# PMU.net
KiCad netlist of a schematic drawn in Altium Designer
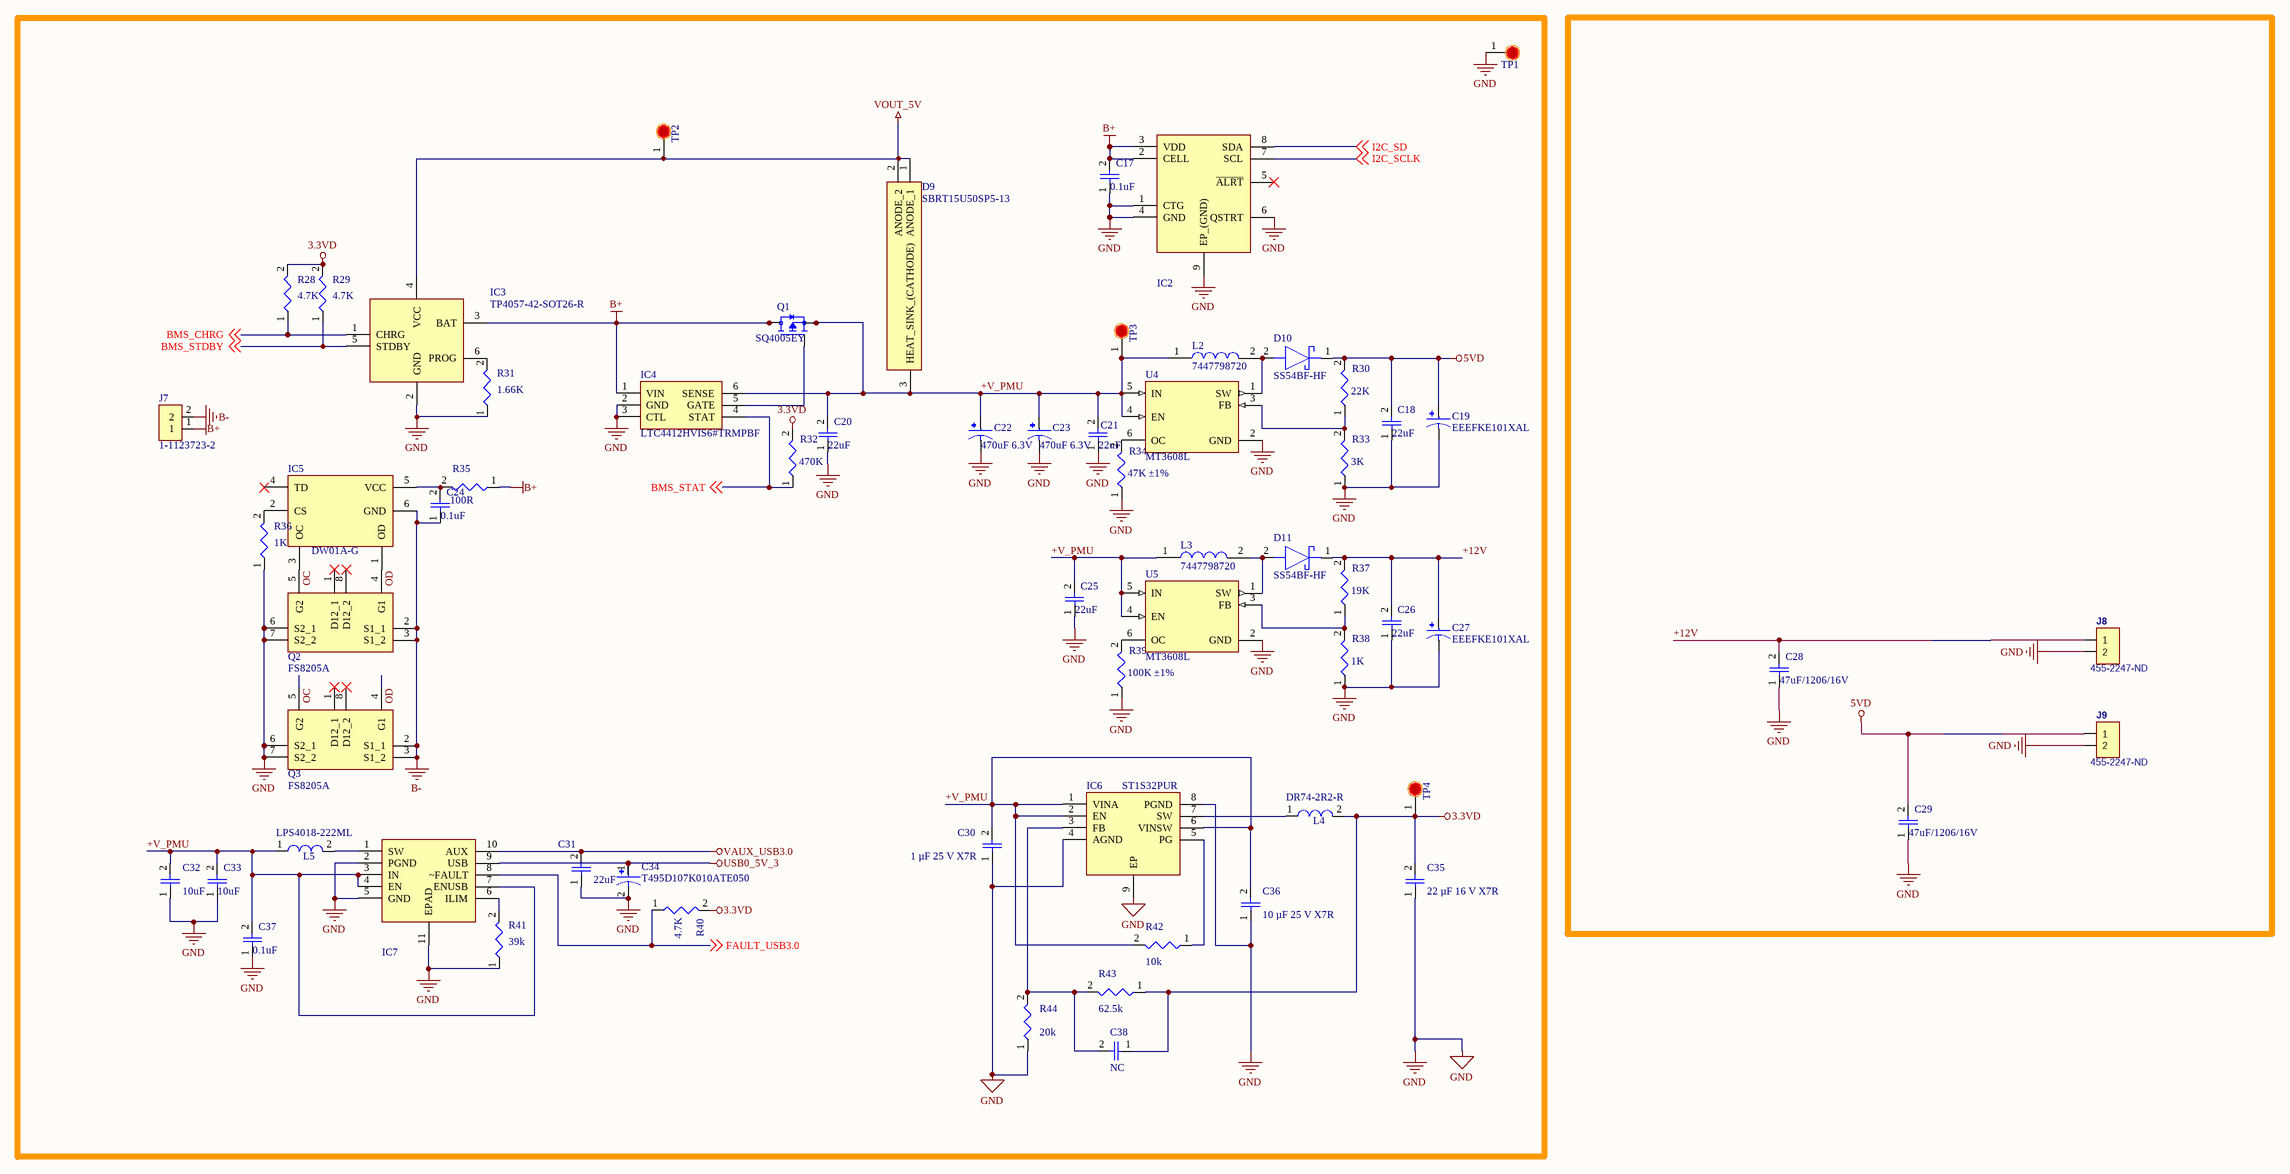
[diagram p0: PMU.SchDoc]

(export (version "E")
  (design (tool "Eeschema 10.0.6"))
  (components
    (comp (ref "C17") (value "0.1uF") (footprint "0603-C") (libsource (lib "OOLITEV8") (part "CAP")))
    (comp (ref "C18") (value "22uF") (footprint "1206-C") (libsource (lib "OOLITEV8") (part "CAP")))
    (comp (ref "C19")
      (value "EEEFKE101XAL")
      (footprint "CAP_EEEFKE101XAL")
      (description "CAP ALUM 100UF 20% 25V SMD")
      (fields (field (name "MF") "Panasonic") (field (name "DIGI-KEY_PART_NUMBER") "10-EEE-FKE101XALCT-ND"))
      (libsource (lib "OOLITEV8") (part "EEEFKE101XAL"))
    )
    (comp (ref "C20") (value "22uF") (footprint "0603-C") (libsource (lib "OOLITEV8") (part "CAP")))
    (comp (ref "C21") (value "22uF") (footprint "0603-C") (libsource (lib "OOLITEV8") (part "CAP")))
    (comp (ref "C22")
      (value "470uF 6.3V")
      (footprint "CAP_EEEFK0J471P")
      (libsource (lib "OOLITEV8") (part "EEEFK0J471P"))
    )
    (comp (ref "C23")
      (value "470uF 6.3V")
      (footprint "CAP_EEEFK0J471P")
      (libsource (lib "OOLITEV8") (part "EEEFK0J471P"))
    )
    (comp (ref "C24") (value "0.1uF") (footprint "0603-C") (libsource (lib "OOLITEV8") (part "CAP")))
    (comp (ref "C25") (value "22uF") (footprint "0603-C") (libsource (lib "OOLITEV8") (part "CAP")))
    (comp (ref "C26") (value "22uF") (footprint "1206-C") (libsource (lib "OOLITEV8") (part "CAP")))
    (comp (ref "C27")
      (value "EEEFKE101XAL")
      (footprint "CAP_EEEFKE101XAL")
      (description "CAP ALUM 100UF 20% 25V SMD")
      (fields (field (name "MF") "Panasonic") (field (name "DIGI-KEY_PART_NUMBER") "10-EEE-FKE101XALCT-ND"))
      (libsource (lib "OOLITEV8") (part "EEEFKE101XAL"))
    )
    (comp (ref "C28") (value "47uF/1206/16V") (footprint "1206-C") (libsource (lib "OOLITEV8") (part "CAP")))
    (comp (ref "C29") (value "47uF/1206/16V") (footprint "1206-C") (libsource (lib "OOLITEV8") (part "CAP")))
    (comp (ref "C30") (value "1 µF 25 V X7R") (footprint "0603-C") (libsource (lib "OOLITEV8") (part "CAP")))
    (comp (ref "C31") (value "22uF") (footprint "1210-C") (libsource (lib "OOLITEV8") (part "CAP")))
    (comp (ref "C32") (value "10uF") (footprint "1210-C") (libsource (lib "OOLITEV8") (part "CAP")))
    (comp (ref "C33") (value "10uF") (footprint "0805-C") (libsource (lib "OOLITEV8") (part "CAP")))
    (comp (ref "C34")
      (value "T495D107K010ATE050")
      (footprint "CAP_4TAE470ML")
      (description "Cap Tant Solid 100uF 10V D CASE 10% (7.3 X 4.3 X 2.8mm) SMD 7343-31 0.05 Ohm 125°C T/R")
      (fields (field (name "MANUFACTURER") "KEMET") (field (name "TOLERANCE") "10%"))
      (libsource (lib "OOLITEV8") (part "T495D107K010ATE050"))
    )
    (comp (ref "C35") (value "22 µF 16 V X7R") (footprint "1210-C") (libsource (lib "OOLITEV8") (part "CAP")))
    (comp (ref "C36") (value "10 µF 25 V X7R") (footprint "1210-C") (libsource (lib "OOLITEV8") (part "CAP")))
    (comp (ref "C37") (value "0.1uF") (footprint "0603-C") (libsource (lib "OOLITEV8") (part "CAP")))
    (comp (ref "C38") (value "NC") (footprint "0603-C") (libsource (lib "OOLITEV8") (part "CAP")))
    (comp (ref "D9")
      (value "SBRT15U50SP5-13")
      (footprint "SamacSys:POWERDI5")
      (description "Diode")
      (fields (field (name "MOUSER PART NUMBER") "621-SBRT15U50SP5-13"))
      (libsource (lib "*") (part "SBRT15U50SP5-13"))
    )
    (comp (ref "D10")
      (value "SS54BF-HF")
      (footprint "SODFL5336X130N")
      (description "Schottky Diode")
      (fields (field (name "MOUSER PART NUMBER") "750-SS54BF-HF"))
      (libsource (lib "OOLITEV8") (part "SS54BF-HF"))
    )
    (comp (ref "D11")
      (value "SS54BF-HF")
      (footprint "SODFL5336X130N")
      (description "Schottky Diode")
      (fields (field (name "MOUSER PART NUMBER") "750-SS54BF-HF"))
      (libsource (lib "OOLITEV8") (part "SS54BF-HF"))
    )
    (comp (ref "IC2")
      (value "MAX17048G+T10")
      (footprint "SON50P200X200X80-9N-D")
      (description "Integrated Circuit")
      (fields (field (name "MOUSER PART NUMBER") "700-MAX17048G+T10"))
      (libsource (lib "OOLITEV8") (part "MAX17048G+T10"))
    )
    (comp (ref "IC3")
      (value "TP4057-42-SOT26-R")
      (footprint "SOT95P280X125-6N")
      (description "Integrated Circuit")
      (libsource (lib "OOLITEV8") (part "TP4057-42-SOT26-R"))
    )
    (comp (ref "IC4")
      (value "LTC4412HVIS6#TRMPBF")
      (footprint "SOT95P280X100-6N")
      (description "Integrated Circuit")
      (fields (field (name "MOUSER PART NUMBER") "584-C4412HVIS6TRMPBF"))
      (libsource (lib "OOLITEV8") (part "LTC4412HVIS6#TRMPBF"))
    )
    (comp (ref "IC5")
      (value "DW01A-G")
      (footprint "SOT95P280X135-6N")
      (description "Integrated Circuit")
      (libsource (lib "OOLITEV8") (part "DW01A-G"))
    )
    (comp (ref "IC6")
      (value "ST1S32PUR")
      (footprint "SON80P400X400X100-9N-D")
      (description "Integrated Circuit")
      (fields (field (name "MOUSER PART NUMBER") "511-ST1S32PUR"))
      (libsource (lib "OOLITEV8") (part "ST1S32PUR"))
    )
    (comp (ref "IC7")
      (value "TPS2500DRCT")
      (footprint "SON50P300X300X100-11N")
      (description "Integrated Circuit")
      (fields (field (name "MOUSER PART NUMBER") "595-TPS2500DRCT"))
      (libsource (lib "OOLITEV8") (part "TPS2500DRCT"))
    )
    (comp (ref "J7")
      (value "1-1123723-2")
      (footprint "TE_1-1123723-2")
      (description "3.96 EP HDR ASSY 2P_NATURAL_")
      (fields (field (name "MF") "TE Connectivity") (field (name "DIGI-KEY_PART_NUMBER") "A111830-ND"))
      (libsource (lib "1-1123723-2") (part "1-1123723-2"))
    )
    (comp (ref "J8")
      (value "455-2247-ND")
      (footprint "CON_HDR1x2")
      (libsource (lib "OOLITEV8") (part "CON_HDR1x2"))
    )
    (comp (ref "J9")
      (value "455-2247-ND")
      (footprint "CON_HDR1x2")
      (libsource (lib "OOLITEV8") (part "CON_HDR1x2"))
    )
    (comp (ref "L2")
      (value "7447798720")
      (footprint "CDRH103RNP6R8NCB")
      (description "Fixed Ind 7.2UH 7.9A 12.8 Mohm")
      (fields (field (name "MANUFACTURER") "Wurth Electronics") (field (name "TOLERANCE") "30%"))
      (libsource (lib "OOLITEV8") (part "7447798720"))
    )
    (comp (ref "L3")
      (value "7447798720")
      (footprint "CDRH103RNP6R8NCB")
      (description "Fixed Ind 7.2UH 7.9A 12.8 Mohm")
      (fields (field (name "MANUFACTURER") "Wurth Electronics") (field (name "TOLERANCE") "30%"))
      (libsource (lib "OOLITEV8") (part "7447798720"))
    )
    (comp (ref "L4")
      (value "DR74-2R2-R")
      (footprint "INDM7676X435N")
      (libsource (lib "OOLITEV8") (part "DR74-2R2-R"))
    )
    (comp (ref "L5")
      (value "LPS4018-222ML")
      (footprint "VLC5045")
      (libsource (lib "OOLITEV8") (part "IND/VLC5045"))
    )
    (comp (ref "Q1")
      (value "SQ4005EY")
      (footprint "SOIC127P600X175-8N")
      (description "MOSFET P Ch -12Vds 8Vgs")
      (libsource (lib "IIOT_GATEWAY_MT7621") (part "SQ4005EY"))
    )
    (comp (ref "Q2")
      (value "FS8205A")
      (footprint "SOP65P640X120-8N")
      (description "Transistor")
      (libsource (lib "OOLITEV8") (part "FS8205A"))
    )
    (comp (ref "Q3")
      (value "FS8205A")
      (footprint "SOP65P640X120-8N")
      (description "Transistor")
      (libsource (lib "OOLITEV8_0_2-DEV-V1_1_17") (part "FS8205A"))
    )
    (comp (ref "R28") (value "4.7K") (footprint "0402-R") (libsource (lib "OOLITEV8") (part "Res")))
    (comp (ref "R29") (value "4.7K") (footprint "0402-R") (libsource (lib "OOLITEV8") (part "Res")))
    (comp (ref "R30") (value "22K") (footprint "0603-R") (libsource (lib "OOLITEV8") (part "Res")))
    (comp (ref "R31") (value "1.66K") (footprint "0603-R") (libsource (lib "OOLITEV8") (part "Res")))
    (comp (ref "R32") (value "470K") (footprint "0402-R") (libsource (lib "OOLITEV8") (part "Res")))
    (comp (ref "R33") (value "3K") (footprint "0603-R") (libsource (lib "OOLITEV8") (part "Res")))
    (comp (ref "R34") (value "47K ±1%") (footprint "0603-R") (libsource (lib "OOLITEV8") (part "Res")))
    (comp (ref "R35") (value "100R") (footprint "0603-R") (libsource (lib "OOLITEV8") (part "Res")))
    (comp (ref "R36") (value "1K") (footprint "0603-R") (libsource (lib "OOLITEV8") (part "Res")))
    (comp (ref "R37") (value "19K") (footprint "0603-R") (libsource (lib "OOLITEV8") (part "Res")))
    (comp (ref "R38") (value "1K") (footprint "0603-R") (libsource (lib "OOLITEV8") (part "Res")))
    (comp (ref "R39") (value "100K ±1%") (footprint "0603-R") (libsource (lib "OOLITEV8") (part "Res")))
    (comp (ref "R40") (value "4.7K") (footprint "0402-R") (libsource (lib "OOLITEV8") (part "Res")))
    (comp (ref "R41") (value "39k") (footprint "0603-R") (libsource (lib "OOLITEV8") (part "Res")))
    (comp (ref "R42") (value "10k") (footprint "0603-R") (libsource (lib "OOLITEV8") (part "Res")))
    (comp (ref "R43") (value "62.5k") (footprint "0603-R") (libsource (lib "OOLITEV8") (part "Res")))
    (comp (ref "R44") (value "20k") (footprint "0603-R") (libsource (lib "OOLITEV8") (part "Res")))
    (comp (ref "TP1") (value "TP") (footprint "TP_SMD") (libsource (lib "OOLITEV8") (part "Test Pad")))
    (comp (ref "TP2") (value "TP") (footprint "TP_SMD") (libsource (lib "OOLITEV8") (part "Test Pad")))
    (comp (ref "TP3") (value "TP") (footprint "TP_SMD") (libsource (lib "OOLITEV8") (part "Test Pad")))
    (comp (ref "TP4") (value "TP") (footprint "TP_SMD") (libsource (lib "OOLITEV8") (part "Test Pad")))
    (comp (ref "U4")
      (value "MT3608L")
      (footprint "SOT95P280X145-6N")
      (description "High Efficiency 1.2MHz2A Step Up Converter")
      (fields (field (name "MF") "Aerosemi Technology Co., Ltd") (field (name "MP") "MT3608"))
      (libsource (lib "OOLITEV8") (part "MT3608L"))
    )
    (comp (ref "U5")
      (value "MT3608L")
      (footprint "SOT95P280X145-6N")
      (description "High Efficiency 1.2MHz2A Step Up Converter")
      (fields (field (name "MF") "Aerosemi Technology Co., Ltd") (field (name "MP") "MT3608"))
      (libsource (lib "OOLITEV8") (part "MT3608L"))
    )
  )
  (nets
    (net (code "1") (name "/+12V") (class "Default")
      (node (ref "C26") (pin "2") (pinfunction "2_2") (pintype "passive"))
      (node (ref "C27") (pin "1") (pinfunction "1_1") (pintype "passive"))
      (node (ref "C28") (pin "2") (pinfunction "2_2") (pintype "passive"))
      (node (ref "D11") (pin "1") (pinfunction "K_1") (pintype "passive"))
      (node (ref "J8") (pin "1") (pinfunction "1_1") (pintype "passive"))
      (node (ref "R37") (pin "2") (pinfunction "2_2") (pintype "passive"))
    )
    (net (code "2") (name "/+V_PMU") (class "Default")
      (node (ref "C20") (pin "2") (pinfunction "2_2") (pintype "passive"))
      (node (ref "C21") (pin "2") (pinfunction "2_2") (pintype "passive"))
      (node (ref "C22") (pin "1") (pinfunction "1_1") (pintype "passive"))
      (node (ref "C23") (pin "1") (pinfunction "1_1") (pintype "passive"))
      (node (ref "C25") (pin "2") (pinfunction "2_2") (pintype "passive"))
      (node (ref "C30") (pin "2") (pinfunction "2_2") (pintype "passive"))
      (node (ref "C32") (pin "2") (pinfunction "2_2") (pintype "passive"))
      (node (ref "C33") (pin "2") (pinfunction "2_2") (pintype "passive"))
      (node (ref "C36") (pin "2") (pinfunction "2_2") (pintype "passive"))
      (node (ref "C37") (pin "2") (pinfunction "2_2") (pintype "passive"))
      (node (ref "D9") (pin "3") (pinfunction "HEAT_SINK_(CATHODE)_3") (pintype "passive"))
      (node (ref "IC4") (pin "6") (pinfunction "SENSE_6") (pintype "passive"))
      (node (ref "IC6") (pin "1") (pinfunction "VINA_1") (pintype "passive"))
      (node (ref "IC6") (pin "2") (pinfunction "EN_2") (pintype "passive"))
      (node (ref "IC6") (pin "6") (pinfunction "VINSW_6") (pintype "passive"))
      (node (ref "IC7") (pin "3") (pinfunction "IN_3") (pintype "passive"))
      (node (ref "IC7") (pin "4") (pinfunction "EN_4") (pintype "passive"))
      (node (ref "IC7") (pin "7") (pinfunction "ENUSB_7") (pintype "passive"))
      (node (ref "L2") (pin "1") (pinfunction "1_1") (pintype "passive"))
      (node (ref "L3") (pin "1") (pinfunction "1_1") (pintype "passive"))
      (node (ref "L5") (pin "1") (pinfunction "1_1") (pintype "passive"))
      (node (ref "Q1") (pin "1") (pinfunction "S_1") (pintype "passive"))
      (node (ref "Q1") (pin "2") (pinfunction "S_2") (pintype "passive"))
      (node (ref "Q1") (pin "3") (pinfunction "S_3") (pintype "passive"))
      (node (ref "R42") (pin "2") (pinfunction "2_2") (pintype "passive"))
      (node (ref "TP3") (pin "1") (pinfunction "1_1") (pintype "passive"))
      (node (ref "U4") (pin "4") (pinfunction "EN_4") (pintype "input"))
      (node (ref "U4") (pin "5") (pinfunction "IN_5") (pintype "input"))
      (node (ref "U5") (pin "4") (pinfunction "EN_4") (pintype "input"))
      (node (ref "U5") (pin "5") (pinfunction "IN_5") (pintype "input"))
    )
    (net (code "3") (name "/OC") (class "Default")
      (node (ref "IC5") (pin "3") (pinfunction "OC_3") (pintype "passive"))
      (node (ref "Q2") (pin "5") (pinfunction "G2_5") (pintype "passive"))
      (node (ref "Q3") (pin "5") (pinfunction "G2_5") (pintype "passive"))
    )
    (net (code "4") (name "/OD") (class "Default")
      (node (ref "IC5") (pin "1") (pinfunction "OD_1") (pintype "passive"))
      (node (ref "Q2") (pin "4") (pinfunction "G1_4") (pintype "passive"))
      (node (ref "Q3") (pin "4") (pinfunction "G1_4") (pintype "passive"))
    )
    (net (code "5") (name "3.3VD") (class "Default")
      (node (ref "C35") (pin "2") (pinfunction "2_2") (pintype "passive"))
      (node (ref "C38") (pin "1") (pinfunction "1_1") (pintype "passive"))
      (node (ref "L4") (pin "2") (pinfunction "2_2") (pintype "passive"))
      (node (ref "R28") (pin "2") (pinfunction "2_2") (pintype "passive"))
      (node (ref "R29") (pin "2") (pinfunction "2_2") (pintype "passive"))
      (node (ref "R32") (pin "2") (pinfunction "2_2") (pintype "passive"))
      (node (ref "R40") (pin "2") (pinfunction "2_2") (pintype "passive"))
      (node (ref "R43") (pin "1") (pinfunction "1_1") (pintype "passive"))
      (node (ref "TP4") (pin "1") (pinfunction "1_1") (pintype "passive"))
    )
    (net (code "6") (name "5VD") (class "Default")
      (node (ref "C18") (pin "2") (pinfunction "2_2") (pintype "passive"))
      (node (ref "C19") (pin "1") (pinfunction "1_1") (pintype "passive"))
      (node (ref "C29") (pin "2") (pinfunction "2_2") (pintype "passive"))
      (node (ref "D10") (pin "1") (pinfunction "K_1") (pintype "passive"))
      (node (ref "J9") (pin "1") (pinfunction "1_1") (pintype "passive"))
      (node (ref "R30") (pin "2") (pinfunction "2_2") (pintype "passive"))
    )
    (net (code "7") (name "B+") (class "Default")
      (node (ref "C17") (pin "2") (pinfunction "2_2") (pintype "passive"))
      (node (ref "IC2") (pin "2") (pinfunction "CELL_2") (pintype "passive"))
      (node (ref "IC2") (pin "3") (pinfunction "VDD_3") (pintype "passive"))
      (node (ref "IC3") (pin "3") (pinfunction "BAT_3") (pintype "passive"))
      (node (ref "IC4") (pin "1") (pinfunction "VIN_1") (pintype "passive"))
      (node (ref "J7") (pin "1") (pinfunction "1_1") (pintype "passive"))
      (node (ref "Q1") (pin "5") (pinfunction "D_5") (pintype "passive"))
      (node (ref "Q1") (pin "6") (pinfunction "D_6") (pintype "passive"))
      (node (ref "Q1") (pin "7") (pinfunction "D_7") (pintype "passive"))
      (node (ref "Q1") (pin "8") (pinfunction "D_8") (pintype "passive"))
      (node (ref "R35") (pin "1") (pinfunction "1_1") (pintype "passive"))
    )
    (net (code "8") (name "B-") (class "Default")
      (node (ref "C24") (pin "1") (pinfunction "1_1") (pintype "passive"))
      (node (ref "IC5") (pin "6") (pinfunction "GND_6") (pintype "passive"))
      (node (ref "J7") (pin "2") (pinfunction "2_2") (pintype "passive"))
      (node (ref "Q2") (pin "2") (pinfunction "S1_1_2") (pintype "passive"))
      (node (ref "Q2") (pin "3") (pinfunction "S1_2_3") (pintype "passive"))
      (node (ref "Q3") (pin "2") (pinfunction "S1_1_2") (pintype "passive"))
      (node (ref "Q3") (pin "3") (pinfunction "S1_2_3") (pintype "passive"))
    )
    (net (code "9") (name "BMS_CHRG") (class "Default")
      (node (ref "IC3") (pin "1") (pinfunction "CHRG_1") (pintype "passive"))
      (node (ref "R28") (pin "1") (pinfunction "1_1") (pintype "passive"))
    )
    (net (code "10") (name "BMS_STAT") (class "Default")
      (node (ref "IC4") (pin "4") (pinfunction "STAT_4") (pintype "passive"))
      (node (ref "R32") (pin "1") (pinfunction "1_1") (pintype "passive"))
    )
    (net (code "11") (name "BMS_STDBY") (class "Default")
      (node (ref "IC3") (pin "5") (pinfunction "STDBY_5") (pintype "passive"))
      (node (ref "R29") (pin "1") (pinfunction "1_1") (pintype "passive"))
    )
    (net (code "12") (name "FAULT_USB3.0") (class "Default")
      (node (ref "IC7") (pin "8") (pinfunction "~FAULT_8") (pintype "passive"))
      (node (ref "R40") (pin "1") (pinfunction "1_1") (pintype "passive"))
    )
    (net (code "13") (name "GND") (class "Default")
      (node (ref "C17") (pin "1") (pinfunction "1_1") (pintype "passive"))
      (node (ref "C18") (pin "1") (pinfunction "1_1") (pintype "passive"))
      (node (ref "C19") (pin "2") (pinfunction "2_2") (pintype "passive"))
      (node (ref "C20") (pin "1") (pinfunction "1_1") (pintype "passive"))
      (node (ref "C21") (pin "1") (pinfunction "1_1") (pintype "passive"))
      (node (ref "C22") (pin "2") (pinfunction "2_2") (pintype "passive"))
      (node (ref "C23") (pin "2") (pinfunction "2_2") (pintype "passive"))
      (node (ref "C25") (pin "1") (pinfunction "1_1") (pintype "passive"))
      (node (ref "C26") (pin "1") (pinfunction "1_1") (pintype "passive"))
      (node (ref "C27") (pin "2") (pinfunction "2_2") (pintype "passive"))
      (node (ref "C28") (pin "1") (pinfunction "1_1") (pintype "passive"))
      (node (ref "C29") (pin "1") (pinfunction "1_1") (pintype "passive"))
      (node (ref "C30") (pin "1") (pinfunction "1_1") (pintype "passive"))
      (node (ref "C31") (pin "1") (pinfunction "1_1") (pintype "passive"))
      (node (ref "C32") (pin "1") (pinfunction "1_1") (pintype "passive"))
      (node (ref "C33") (pin "1") (pinfunction "1_1") (pintype "passive"))
      (node (ref "C34") (pin "2") (pinfunction "2_2") (pintype "passive"))
      (node (ref "C35") (pin "1") (pinfunction "1_1") (pintype "passive"))
      (node (ref "C36") (pin "1") (pinfunction "1_1") (pintype "passive"))
      (node (ref "C37") (pin "1") (pinfunction "1_1") (pintype "passive"))
      (node (ref "IC2") (pin "1") (pinfunction "CTG_1") (pintype "passive"))
      (node (ref "IC2") (pin "4") (pinfunction "GND_4") (pintype "passive"))
      (node (ref "IC2") (pin "6") (pinfunction "QSTRT_6") (pintype "passive"))
      (node (ref "IC2") (pin "9") (pinfunction "EP_(GND)_9") (pintype "passive"))
      (node (ref "IC3") (pin "2") (pinfunction "GND_2") (pintype "passive"))
      (node (ref "IC4") (pin "2") (pinfunction "GND_2") (pintype "passive"))
      (node (ref "IC4") (pin "3") (pinfunction "CTL_3") (pintype "passive"))
      (node (ref "IC6") (pin "4") (pinfunction "AGND_4") (pintype "passive"))
      (node (ref "IC6") (pin "8") (pinfunction "PGND_8") (pintype "passive"))
      (node (ref "IC6") (pin "9") (pinfunction "EP_9") (pintype "passive"))
      (node (ref "IC7") (pin "11") (pinfunction "EPAD_11") (pintype "passive"))
      (node (ref "IC7") (pin "2") (pinfunction "PGND_2") (pintype "passive"))
      (node (ref "IC7") (pin "5") (pinfunction "GND_5") (pintype "passive"))
      (node (ref "J8") (pin "2") (pinfunction "2_2") (pintype "passive"))
      (node (ref "J9") (pin "2") (pinfunction "2_2") (pintype "passive"))
      (node (ref "Q2") (pin "6") (pinfunction "S2_1_6") (pintype "passive"))
      (node (ref "Q2") (pin "7") (pinfunction "S2_2_7") (pintype "passive"))
      (node (ref "Q3") (pin "6") (pinfunction "S2_1_6") (pintype "passive"))
      (node (ref "Q3") (pin "7") (pinfunction "S2_2_7") (pintype "passive"))
      (node (ref "R31") (pin "1") (pinfunction "1_1") (pintype "passive"))
      (node (ref "R33") (pin "1") (pinfunction "1_1") (pintype "passive"))
      (node (ref "R34") (pin "1") (pinfunction "1_1") (pintype "passive"))
      (node (ref "R36") (pin "1") (pinfunction "1_1") (pintype "passive"))
      (node (ref "R38") (pin "1") (pinfunction "1_1") (pintype "passive"))
      (node (ref "R39") (pin "1") (pinfunction "1_1") (pintype "passive"))
      (node (ref "R41") (pin "1") (pinfunction "1_1") (pintype "passive"))
      (node (ref "R44") (pin "1") (pinfunction "1_1") (pintype "passive"))
      (node (ref "TP1") (pin "1") (pinfunction "1_1") (pintype "passive"))
      (node (ref "U4") (pin "2") (pinfunction "GND_2") (pintype "power_in"))
      (node (ref "U5") (pin "2") (pinfunction "GND_2") (pintype "power_in"))
    )
    (net (code "14") (name "I2C_SCLK") (class "Default")
      (node (ref "IC2") (pin "7") (pinfunction "SCL_7") (pintype "passive"))
    )
    (net (code "15") (name "I2C_SD") (class "Default")
      (node (ref "IC2") (pin "8") (pinfunction "SDA_8") (pintype "passive"))
    )
    (net (code "16") (name "Net-(D10-A)") (class "Default")
      (node (ref "D10") (pin "2") (pinfunction "A_2") (pintype "passive"))
      (node (ref "L2") (pin "2") (pinfunction "2_2") (pintype "passive"))
      (node (ref "U4") (pin "1") (pinfunction "SW_1") (pintype "output"))
    )
    (net (code "17") (name "Net-(D11-A)") (class "Default")
      (node (ref "D11") (pin "2") (pinfunction "A_2") (pintype "passive"))
      (node (ref "L3") (pin "2") (pinfunction "2_2") (pintype "passive"))
      (node (ref "U5") (pin "1") (pinfunction "SW_1") (pintype "output"))
    )
    (net (code "18") (name "Net-(IC3-PROG)") (class "Default")
      (node (ref "IC3") (pin "6") (pinfunction "PROG_6") (pintype "passive"))
      (node (ref "R31") (pin "2") (pinfunction "2_2") (pintype "passive"))
    )
    (net (code "19") (name "Net-(IC4-GATE)") (class "Default")
      (node (ref "IC4") (pin "5") (pinfunction "GATE_5") (pintype "passive"))
      (node (ref "Q1") (pin "4") (pinfunction "G_4") (pintype "passive"))
    )
    (net (code "20") (name "Net-(IC5-CS)") (class "Default")
      (node (ref "IC5") (pin "2") (pinfunction "CS_2") (pintype "passive"))
      (node (ref "R36") (pin "2") (pinfunction "2_2") (pintype "passive"))
    )
    (net (code "21") (name "Net-(IC5-VCC)") (class "Default")
      (node (ref "C24") (pin "2") (pinfunction "2_2") (pintype "passive"))
      (node (ref "IC5") (pin "5") (pinfunction "VCC_5") (pintype "passive"))
      (node (ref "R35") (pin "2") (pinfunction "2_2") (pintype "passive"))
    )
    (net (code "22") (name "Net-(IC6-FB)") (class "Default")
      (node (ref "C38") (pin "2") (pinfunction "2_2") (pintype "passive"))
      (node (ref "IC6") (pin "3") (pinfunction "FB_3") (pintype "passive"))
      (node (ref "R43") (pin "2") (pinfunction "2_2") (pintype "passive"))
      (node (ref "R44") (pin "2") (pinfunction "2_2") (pintype "passive"))
    )
    (net (code "23") (name "Net-(IC6-PG)") (class "Default")
      (node (ref "IC6") (pin "5") (pinfunction "PG_5") (pintype "passive"))
      (node (ref "R42") (pin "1") (pinfunction "1_1") (pintype "passive"))
    )
    (net (code "24") (name "Net-(IC6-SW)") (class "Default")
      (node (ref "IC6") (pin "7") (pinfunction "SW_7") (pintype "passive"))
      (node (ref "L4") (pin "1") (pinfunction "1_1") (pintype "passive"))
    )
    (net (code "25") (name "Net-(IC7-ILIM)") (class "Default")
      (node (ref "IC7") (pin "6") (pinfunction "ILIM_6") (pintype "passive"))
      (node (ref "R41") (pin "2") (pinfunction "2_2") (pintype "passive"))
    )
    (net (code "26") (name "Net-(IC7-SW)") (class "Default")
      (node (ref "IC7") (pin "1") (pinfunction "SW_1") (pintype "passive"))
      (node (ref "L5") (pin "2") (pinfunction "2_2") (pintype "passive"))
    )
    (net (code "27") (name "Net-(U4-FB)") (class "Default")
      (node (ref "R30") (pin "1") (pinfunction "1_1") (pintype "passive"))
      (node (ref "R33") (pin "2") (pinfunction "2_2") (pintype "passive"))
      (node (ref "U4") (pin "3") (pinfunction "FB_3") (pintype "input"))
    )
    (net (code "28") (name "Net-(U4-OC)") (class "Default")
      (node (ref "R34") (pin "2") (pinfunction "2_2") (pintype "passive"))
      (node (ref "U4") (pin "6") (pinfunction "OC_6") (pintype "passive"))
    )
    (net (code "29") (name "Net-(U5-FB)") (class "Default")
      (node (ref "R37") (pin "1") (pinfunction "1_1") (pintype "passive"))
      (node (ref "R38") (pin "2") (pinfunction "2_2") (pintype "passive"))
      (node (ref "U5") (pin "3") (pinfunction "FB_3") (pintype "input"))
    )
    (net (code "30") (name "Net-(U5-OC)") (class "Default")
      (node (ref "R39") (pin "2") (pinfunction "2_2") (pintype "passive"))
      (node (ref "U5") (pin "6") (pinfunction "OC_6") (pintype "passive"))
    )
    (net (code "31") (name "USB0_5V_3") (class "Default")
      (node (ref "C34") (pin "1") (pinfunction "1_1") (pintype "passive"))
      (node (ref "IC7") (pin "9") (pinfunction "USB_9") (pintype "passive"))
    )
    (net (code "32") (name "VAUX_USB3.0") (class "Default")
      (node (ref "C31") (pin "2") (pinfunction "2_2") (pintype "passive"))
      (node (ref "IC7") (pin "10") (pinfunction "AUX_10") (pintype "passive"))
    )
    (net (code "33") (name "VOUT_5V") (class "Default")
      (node (ref "D9") (pin "1") (pinfunction "ANODE_1_1") (pintype "passive"))
      (node (ref "D9") (pin "2") (pinfunction "ANODE_2_2") (pintype "passive"))
      (node (ref "IC3") (pin "4") (pinfunction "VCC_4") (pintype "passive"))
      (node (ref "TP2") (pin "1") (pinfunction "1_1") (pintype "passive"))
    )
    (net (code "34") (name "unconnected-(IC2-~{ALRT}-Pad5)") (class "Default")
      (node (ref "IC2") (pin "5") (pinfunction "~{ALRT}_5") (pintype "passive+no_connect"))
    )
    (net (code "35") (name "unconnected-(IC5-TD-Pad4)") (class "Default")
      (node (ref "IC5") (pin "4") (pinfunction "TD_4") (pintype "passive+no_connect"))
    )
    (net (code "36") (name "unconnected-(Q2-D12_1-Pad1)") (class "Default")
      (node (ref "Q2") (pin "1") (pinfunction "D12_1_1") (pintype "passive+no_connect"))
    )
    (net (code "37") (name "unconnected-(Q2-D12_2-Pad8)") (class "Default")
      (node (ref "Q2") (pin "8") (pinfunction "D12_2_8") (pintype "passive+no_connect"))
    )
    (net (code "38") (name "unconnected-(Q3-D12_1-Pad1)") (class "Default")
      (node (ref "Q3") (pin "1") (pinfunction "D12_1_1") (pintype "passive+no_connect"))
    )
    (net (code "39") (name "unconnected-(Q3-D12_2-Pad8)") (class "Default")
      (node (ref "Q3") (pin "8") (pinfunction "D12_2_8") (pintype "passive+no_connect"))
    )
  )
)
